# TSOP-II-44_v3.net
KiCad netlist of a schematic drawn in EAGLE
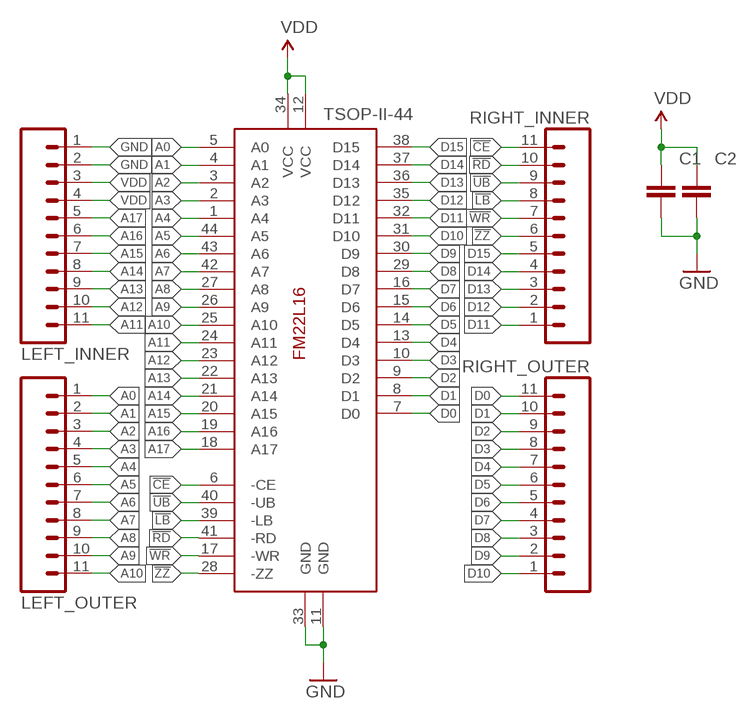
[diagram p0: schematic, sheet 1]

(export (version "E")
  (design (tool "Eeschema 10.0.6"))
  (components
    (comp (ref "C1")
      (value "CAPACITOR_NPOL-0603")
      (footprint "eagle-import:C603")
      (libsource (lib "eagle-import") (part "CAPACITOR_NPOL-0603"))
    )
    (comp (ref "C2")
      (value "CAPACITOR_NPOL-0603")
      (footprint "eagle-import:C603")
      (libsource (lib "eagle-import") (part "CAPACITOR_NPOL-0603"))
    )
    (comp (ref "LEFT_INNER")
      (value "M11PTH")
      (footprint "eagle-import:1X11")
      (libsource (lib "eagle-import") (part "M11PTH"))
    )
    (comp (ref "LEFT_OUTER")
      (value "M11PTH")
      (footprint "eagle-import:1X11")
      (libsource (lib "eagle-import") (part "M11PTH"))
    )
    (comp (ref "RIGHT_INNER")
      (value "M11PTH")
      (footprint "eagle-import:1X11")
      (libsource (lib "eagle-import") (part "M11PTH"))
    )
    (comp (ref "RIGHT_OUTER")
      (value "M11PTH")
      (footprint "eagle-import:1X11")
      (libsource (lib "eagle-import") (part "M11PTH"))
    )
    (comp (ref "TSOP-II-44")
      (value "FM22L16-TG")
      (footprint "eagle-import:TSOPII-44")
      (libsource (lib "eagle-import") (part "FM22L16-TG"))
    )
  )
  (nets
    (net (code "1") (name "/~{CE}") (class "Default")
      (node (ref "RIGHT_INNER") (pin "11") (pinfunction "11_11") (pintype "passive"))
      (node (ref "TSOP-II-44") (pin "6") (pinfunction "-CE_6") (pintype "input"))
    )
    (net (code "2") (name "/~{LB}") (class "Default")
      (node (ref "RIGHT_INNER") (pin "8") (pinfunction "8_8") (pintype "passive"))
      (node (ref "TSOP-II-44") (pin "39") (pinfunction "-LB_39") (pintype "input"))
    )
    (net (code "3") (name "/~{RD}") (class "Default")
      (node (ref "RIGHT_INNER") (pin "10") (pinfunction "10_10") (pintype "passive"))
      (node (ref "TSOP-II-44") (pin "41") (pinfunction "-RD_41") (pintype "input"))
    )
    (net (code "4") (name "/~{UB}") (class "Default")
      (node (ref "RIGHT_INNER") (pin "9") (pinfunction "9_9") (pintype "passive"))
      (node (ref "TSOP-II-44") (pin "40") (pinfunction "-UB_40") (pintype "input"))
    )
    (net (code "5") (name "/~{WR}") (class "Default")
      (node (ref "RIGHT_INNER") (pin "7") (pinfunction "7_7") (pintype "passive"))
      (node (ref "TSOP-II-44") (pin "17") (pinfunction "-WR_17") (pintype "input"))
    )
    (net (code "6") (name "/~{ZZ}") (class "Default")
      (node (ref "RIGHT_INNER") (pin "6") (pinfunction "6_6") (pintype "passive"))
      (node (ref "TSOP-II-44") (pin "28") (pinfunction "-ZZ_28") (pintype "input"))
    )
    (net (code "7") (name "A0") (class "Default")
      (node (ref "LEFT_OUTER") (pin "1") (pinfunction "1_1") (pintype "passive"))
      (node (ref "TSOP-II-44") (pin "5") (pinfunction "A0_5") (pintype "input"))
    )
    (net (code "8") (name "A1") (class "Default")
      (node (ref "LEFT_OUTER") (pin "2") (pinfunction "2_2") (pintype "passive"))
      (node (ref "TSOP-II-44") (pin "4") (pinfunction "A1_4") (pintype "input"))
    )
    (net (code "9") (name "A2") (class "Default")
      (node (ref "LEFT_OUTER") (pin "3") (pinfunction "3_3") (pintype "passive"))
      (node (ref "TSOP-II-44") (pin "3") (pinfunction "A2_3") (pintype "input"))
    )
    (net (code "10") (name "A3") (class "Default")
      (node (ref "LEFT_OUTER") (pin "4") (pinfunction "4_4") (pintype "passive"))
      (node (ref "TSOP-II-44") (pin "2") (pinfunction "A3_2") (pintype "input"))
    )
    (net (code "11") (name "A4") (class "Default")
      (node (ref "LEFT_OUTER") (pin "5") (pinfunction "5_5") (pintype "passive"))
      (node (ref "TSOP-II-44") (pin "1") (pinfunction "A4_1") (pintype "input"))
    )
    (net (code "12") (name "A5") (class "Default")
      (node (ref "LEFT_OUTER") (pin "6") (pinfunction "6_6") (pintype "passive"))
      (node (ref "TSOP-II-44") (pin "44") (pinfunction "A5_44") (pintype "input"))
    )
    (net (code "13") (name "A6") (class "Default")
      (node (ref "LEFT_OUTER") (pin "7") (pinfunction "7_7") (pintype "passive"))
      (node (ref "TSOP-II-44") (pin "43") (pinfunction "A6_43") (pintype "input"))
    )
    (net (code "14") (name "A7") (class "Default")
      (node (ref "LEFT_OUTER") (pin "8") (pinfunction "8_8") (pintype "passive"))
      (node (ref "TSOP-II-44") (pin "42") (pinfunction "A7_42") (pintype "input"))
    )
    (net (code "15") (name "A8") (class "Default")
      (node (ref "LEFT_OUTER") (pin "9") (pinfunction "9_9") (pintype "passive"))
      (node (ref "TSOP-II-44") (pin "27") (pinfunction "A8_27") (pintype "input"))
    )
    (net (code "16") (name "A9") (class "Default")
      (node (ref "LEFT_OUTER") (pin "10") (pinfunction "10_10") (pintype "passive"))
      (node (ref "TSOP-II-44") (pin "26") (pinfunction "A9_26") (pintype "input"))
    )
    (net (code "17") (name "A10") (class "Default")
      (node (ref "LEFT_OUTER") (pin "11") (pinfunction "11_11") (pintype "passive"))
      (node (ref "TSOP-II-44") (pin "25") (pinfunction "A10_25") (pintype "input"))
    )
    (net (code "18") (name "A11") (class "Default")
      (node (ref "LEFT_INNER") (pin "11") (pinfunction "11_11") (pintype "passive"))
      (node (ref "TSOP-II-44") (pin "24") (pinfunction "A11_24") (pintype "input"))
    )
    (net (code "19") (name "A12") (class "Default")
      (node (ref "LEFT_INNER") (pin "10") (pinfunction "10_10") (pintype "passive"))
      (node (ref "TSOP-II-44") (pin "23") (pinfunction "A12_23") (pintype "input"))
    )
    (net (code "20") (name "A13") (class "Default")
      (node (ref "LEFT_INNER") (pin "9") (pinfunction "9_9") (pintype "passive"))
      (node (ref "TSOP-II-44") (pin "22") (pinfunction "A13_22") (pintype "input"))
    )
    (net (code "21") (name "A14") (class "Default")
      (node (ref "LEFT_INNER") (pin "8") (pinfunction "8_8") (pintype "passive"))
      (node (ref "TSOP-II-44") (pin "21") (pinfunction "A14_21") (pintype "input"))
    )
    (net (code "22") (name "A15") (class "Default")
      (node (ref "LEFT_INNER") (pin "7") (pinfunction "7_7") (pintype "passive"))
      (node (ref "TSOP-II-44") (pin "20") (pinfunction "A15_20") (pintype "input"))
    )
    (net (code "23") (name "A16") (class "Default")
      (node (ref "LEFT_INNER") (pin "6") (pinfunction "6_6") (pintype "passive"))
      (node (ref "TSOP-II-44") (pin "19") (pinfunction "A16_19") (pintype "input"))
    )
    (net (code "24") (name "A17") (class "Default")
      (node (ref "LEFT_INNER") (pin "5") (pinfunction "5_5") (pintype "passive"))
      (node (ref "TSOP-II-44") (pin "18") (pinfunction "A17_18") (pintype "input"))
    )
    (net (code "25") (name "D0") (class "Default")
      (node (ref "RIGHT_OUTER") (pin "11") (pinfunction "11_11") (pintype "passive"))
      (node (ref "TSOP-II-44") (pin "7") (pinfunction "D0_7") (pintype "bidirectional"))
    )
    (net (code "26") (name "D1") (class "Default")
      (node (ref "RIGHT_OUTER") (pin "10") (pinfunction "10_10") (pintype "passive"))
      (node (ref "TSOP-II-44") (pin "8") (pinfunction "D1_8") (pintype "bidirectional"))
    )
    (net (code "27") (name "D2") (class "Default")
      (node (ref "RIGHT_OUTER") (pin "9") (pinfunction "9_9") (pintype "passive"))
      (node (ref "TSOP-II-44") (pin "9") (pinfunction "D2_9") (pintype "bidirectional"))
    )
    (net (code "28") (name "D3") (class "Default")
      (node (ref "RIGHT_OUTER") (pin "8") (pinfunction "8_8") (pintype "passive"))
      (node (ref "TSOP-II-44") (pin "10") (pinfunction "D3_10") (pintype "bidirectional"))
    )
    (net (code "29") (name "D4") (class "Default")
      (node (ref "RIGHT_OUTER") (pin "7") (pinfunction "7_7") (pintype "passive"))
      (node (ref "TSOP-II-44") (pin "13") (pinfunction "D4_13") (pintype "bidirectional"))
    )
    (net (code "30") (name "D5") (class "Default")
      (node (ref "RIGHT_OUTER") (pin "6") (pinfunction "6_6") (pintype "passive"))
      (node (ref "TSOP-II-44") (pin "14") (pinfunction "D5_14") (pintype "bidirectional"))
    )
    (net (code "31") (name "D6") (class "Default")
      (node (ref "RIGHT_OUTER") (pin "5") (pinfunction "5_5") (pintype "passive"))
      (node (ref "TSOP-II-44") (pin "15") (pinfunction "D6_15") (pintype "bidirectional"))
    )
    (net (code "32") (name "D7") (class "Default")
      (node (ref "RIGHT_OUTER") (pin "4") (pinfunction "4_4") (pintype "passive"))
      (node (ref "TSOP-II-44") (pin "16") (pinfunction "D7_16") (pintype "bidirectional"))
    )
    (net (code "33") (name "D8") (class "Default")
      (node (ref "RIGHT_OUTER") (pin "3") (pinfunction "3_3") (pintype "passive"))
      (node (ref "TSOP-II-44") (pin "29") (pinfunction "D8_29") (pintype "bidirectional"))
    )
    (net (code "34") (name "D9") (class "Default")
      (node (ref "RIGHT_OUTER") (pin "2") (pinfunction "2_2") (pintype "passive"))
      (node (ref "TSOP-II-44") (pin "30") (pinfunction "D9_30") (pintype "bidirectional"))
    )
    (net (code "35") (name "D10") (class "Default")
      (node (ref "RIGHT_OUTER") (pin "1") (pinfunction "1_1") (pintype "passive"))
      (node (ref "TSOP-II-44") (pin "31") (pinfunction "D10_31") (pintype "bidirectional"))
    )
    (net (code "36") (name "D11") (class "Default")
      (node (ref "RIGHT_INNER") (pin "1") (pinfunction "1_1") (pintype "passive"))
      (node (ref "TSOP-II-44") (pin "32") (pinfunction "D11_32") (pintype "bidirectional"))
    )
    (net (code "37") (name "D12") (class "Default")
      (node (ref "RIGHT_INNER") (pin "2") (pinfunction "2_2") (pintype "passive"))
      (node (ref "TSOP-II-44") (pin "35") (pinfunction "D12_35") (pintype "bidirectional"))
    )
    (net (code "38") (name "D13") (class "Default")
      (node (ref "RIGHT_INNER") (pin "3") (pinfunction "3_3") (pintype "passive"))
      (node (ref "TSOP-II-44") (pin "36") (pinfunction "D13_36") (pintype "bidirectional"))
    )
    (net (code "39") (name "D14") (class "Default")
      (node (ref "RIGHT_INNER") (pin "4") (pinfunction "4_4") (pintype "passive"))
      (node (ref "TSOP-II-44") (pin "37") (pinfunction "D14_37") (pintype "bidirectional"))
    )
    (net (code "40") (name "D15") (class "Default")
      (node (ref "RIGHT_INNER") (pin "5") (pinfunction "5_5") (pintype "passive"))
      (node (ref "TSOP-II-44") (pin "38") (pinfunction "D15_38") (pintype "bidirectional"))
    )
    (net (code "41") (name "GND") (class "Default")
      (node (ref "C1") (pin "2") (pinfunction "2_2") (pintype "passive"))
      (node (ref "C2") (pin "2") (pinfunction "2_2") (pintype "passive"))
      (node (ref "LEFT_INNER") (pin "1") (pinfunction "1_1") (pintype "passive"))
      (node (ref "LEFT_INNER") (pin "2") (pinfunction "2_2") (pintype "passive"))
      (node (ref "TSOP-II-44") (pin "11") (pinfunction "GND_11") (pintype "power_in"))
      (node (ref "TSOP-II-44") (pin "33") (pinfunction "GND_33") (pintype "power_in"))
    )
    (net (code "42") (name "VDD") (class "Default")
      (node (ref "C1") (pin "1") (pinfunction "1_1") (pintype "passive"))
      (node (ref "C2") (pin "1") (pinfunction "1_1") (pintype "passive"))
      (node (ref "LEFT_INNER") (pin "3") (pinfunction "3_3") (pintype "passive"))
      (node (ref "LEFT_INNER") (pin "4") (pinfunction "4_4") (pintype "passive"))
      (node (ref "TSOP-II-44") (pin "12") (pinfunction "VCC_12") (pintype "power_in"))
      (node (ref "TSOP-II-44") (pin "34") (pinfunction "VCC_34") (pintype "power_in"))
    )
  )
)
